# GNSS_BLE.net
KiCad netlist of a schematic drawn in Altium Designer
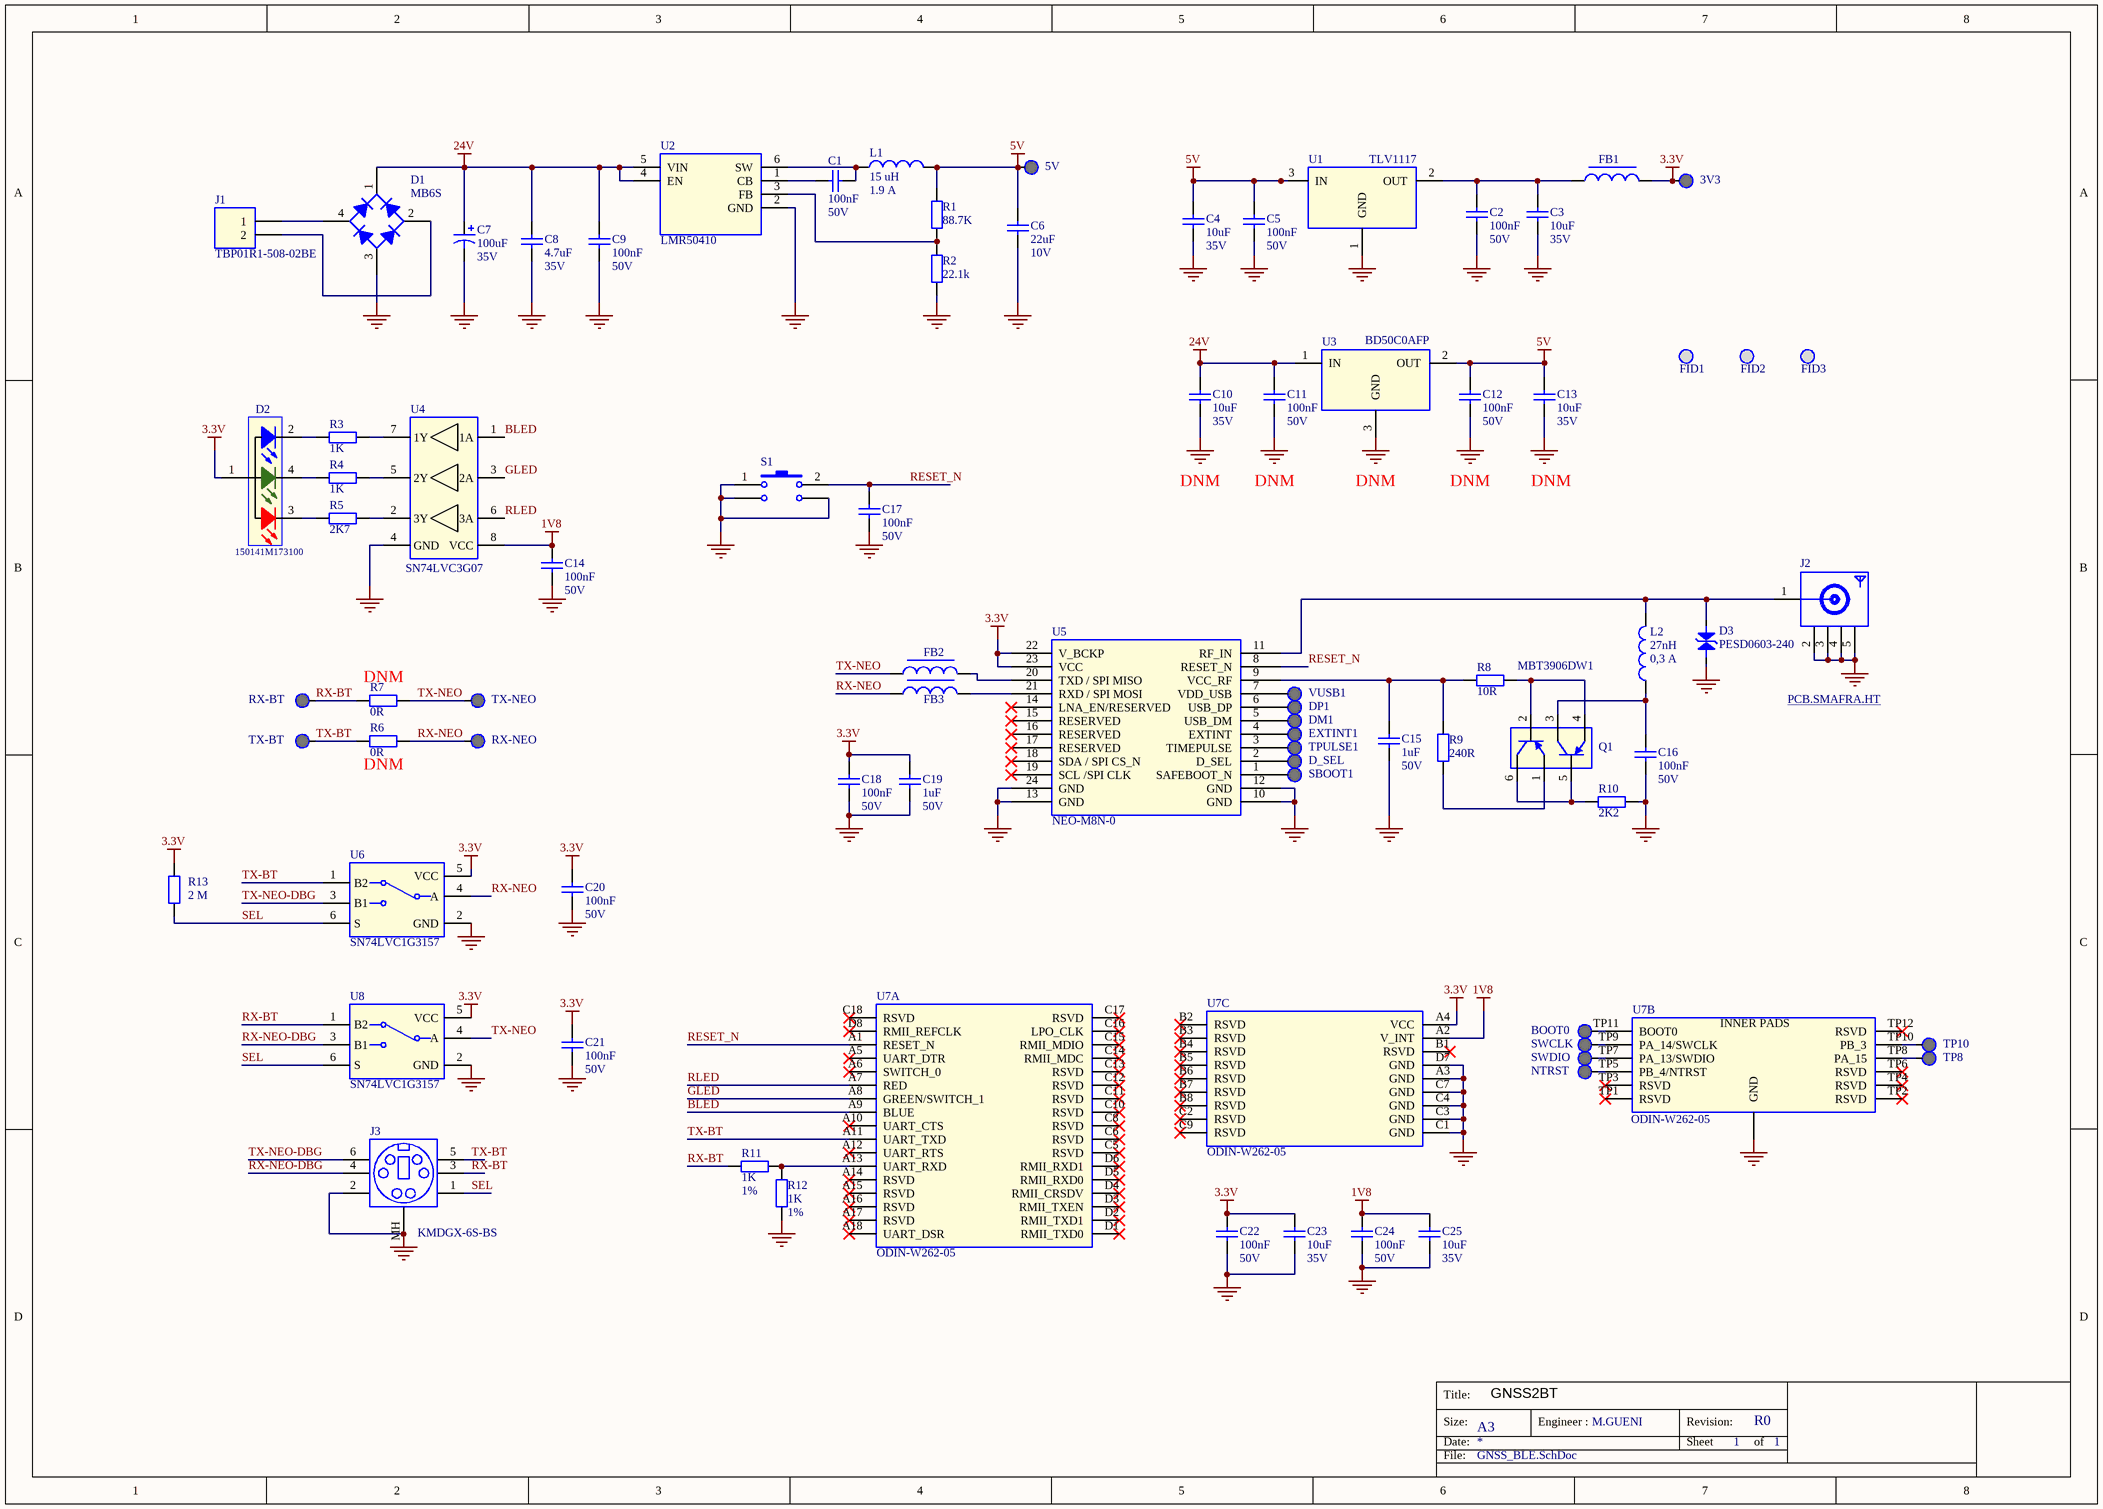
[diagram p0: GNSS_BLE.SchDoc]

(export (version "E")
  (design (tool "Eeschema 10.0.6"))
  (components
    (comp (ref "3V3")
      (value "Test Point")
      (footprint "TP")
      (fields (field (name "PART NUMBER") "MIS-000000001"))
      (libsource (lib "GNSS") (part "TP"))
    )
    (comp (ref "5V")
      (value "Test Point")
      (footprint "TP")
      (fields (field (name "PART NUMBER") "MIS-000000001"))
      (libsource (lib "GNSS") (part "TP"))
    )
    (comp (ref "BOOT0")
      (value "Test Point")
      (footprint "TP")
      (fields (field (name "PART NUMBER") "MIS-000000001"))
      (libsource (lib "GNSS") (part "TP"))
    )
    (comp (ref "C1")
      (value "C0603C104K5RAC3121")
      (footprint "CAPC1608N")
      (fields
        (field (name "PART NUMBER") "CAP-000000001")
        (field (name "VALUE 1") "100nF")
        (field (name "VALUE 2") "50V")
      )
      (libsource (lib "GNSS") (part "Capacitor"))
    )
    (comp (ref "C2")
      (value "C0603C104K5RAC3121")
      (footprint "CAPC1608N")
      (fields
        (field (name "PART NUMBER") "CAP-000000001")
        (field (name "VALUE 1") "100nF")
        (field (name "VALUE 2") "50V")
      )
      (libsource (lib "GNSS") (part "Capacitor"))
    )
    (comp (ref "C3")
      (value "GRM188R6YA106MA73D")
      (footprint "CAPC1608N")
      (fields
        (field (name "PART NUMBER") "CAP-000000003")
        (field (name "VALUE 1") "10uF")
        (field (name "VALUE 2") "35V")
      )
      (libsource (lib "GNSS") (part "Capacitor"))
    )
    (comp (ref "C4")
      (value "GRM188R6YA106MA73D")
      (footprint "CAPC1608N")
      (fields
        (field (name "PART NUMBER") "CAP-000000003")
        (field (name "VALUE 1") "10uF")
        (field (name "VALUE 2") "35V")
      )
      (libsource (lib "GNSS") (part "Capacitor"))
    )
    (comp (ref "C5")
      (value "C0603C104K5RAC3121")
      (footprint "CAPC1608N")
      (fields
        (field (name "PART NUMBER") "CAP-000000001")
        (field (name "VALUE 1") "100nF")
        (field (name "VALUE 2") "50V")
      )
      (libsource (lib "GNSS") (part "Capacitor"))
    )
    (comp (ref "C6")
      (value "GRM188R61A226ME15D")
      (footprint "CAPC1608N")
      (fields
        (field (name "PART NUMBER") "CAP-000000006")
        (field (name "VALUE 1") "22uF")
        (field (name "VALUE 2") "10V")
      )
      (libsource (lib "GNSS") (part "Capacitor"))
    )
    (comp (ref "C7")
      (value "EEEFK1V101XP")
      (footprint "ECAP_SMD_6.3")
      (fields
        (field (name "PART NUMBER") "CAP-000000001")
        (field (name "VALUE 1") "100uF")
        (field (name "VALUE 2") "35V")
      )
      (libsource (lib "GNSS") (part "CPolarized"))
    )
    (comp (ref "C8")
      (value "GRM188R6YA475KE5D")
      (footprint "CAPC1608N")
      (fields
        (field (name "PART NUMBER") "CAP-000000005")
        (field (name "VALUE 1") "4.7uF")
        (field (name "VALUE 2") "35V")
      )
      (libsource (lib "GNSS") (part "Capacitor"))
    )
    (comp (ref "C9")
      (value "C0603C104K5RAC3121")
      (footprint "CAPC1608N")
      (fields
        (field (name "PART NUMBER") "CAP-000000001")
        (field (name "VALUE 1") "100nF")
        (field (name "VALUE 2") "50V")
      )
      (libsource (lib "GNSS") (part "Capacitor"))
    )
    (comp (ref "C10")
      (value "GRM188R6YA106MA73D")
      (footprint "CAPC1608N")
      (fields
        (field (name "PART NUMBER") "CAP-000000003")
        (field (name "VALUE 1") "10uF")
        (field (name "VALUE 2") "35V")
      )
      (libsource (lib "GNSS") (part "Capacitor"))
    )
    (comp (ref "C11")
      (value "C0603C104K5RAC3121")
      (footprint "CAPC1608N")
      (fields
        (field (name "PART NUMBER") "CAP-000000001")
        (field (name "VALUE 1") "100nF")
        (field (name "VALUE 2") "50V")
      )
      (libsource (lib "GNSS") (part "Capacitor"))
    )
    (comp (ref "C12")
      (value "C0603C104K5RAC3121")
      (footprint "CAPC1608N")
      (fields
        (field (name "PART NUMBER") "CAP-000000001")
        (field (name "VALUE 1") "100nF")
        (field (name "VALUE 2") "50V")
      )
      (libsource (lib "GNSS") (part "Capacitor"))
    )
    (comp (ref "C13")
      (value "GRM188R6YA106MA73D")
      (footprint "CAPC1608N")
      (fields
        (field (name "PART NUMBER") "CAP-000000003")
        (field (name "VALUE 1") "10uF")
        (field (name "VALUE 2") "35V")
      )
      (libsource (lib "GNSS") (part "Capacitor"))
    )
    (comp (ref "C14")
      (value "C0603C104K5RAC3121")
      (footprint "CAPC1608N")
      (fields
        (field (name "PART NUMBER") "CAP-000000001")
        (field (name "VALUE 1") "100nF")
        (field (name "VALUE 2") "50V")
      )
      (libsource (lib "GNSS") (part "Capacitor"))
    )
    (comp (ref "C15")
      (value "GRT188R61H105KE13D")
      (footprint "CAPC1608N")
      (fields
        (field (name "PART NUMBER") "CAP-000000004")
        (field (name "VALUE 1") "1uF")
        (field (name "VALUE 2") "50V")
      )
      (libsource (lib "GNSS") (part "Capacitor"))
    )
    (comp (ref "C16")
      (value "C0603C104K5RAC3121")
      (footprint "CAPC1608N")
      (fields
        (field (name "PART NUMBER") "CAP-000000001")
        (field (name "VALUE 1") "100nF")
        (field (name "VALUE 2") "50V")
      )
      (libsource (lib "GNSS") (part "Capacitor"))
    )
    (comp (ref "C17")
      (value "C0603C104K5RAC3121")
      (footprint "CAPC1608N")
      (fields
        (field (name "PART NUMBER") "CAP-000000001")
        (field (name "VALUE 1") "100nF")
        (field (name "VALUE 2") "50V")
      )
      (libsource (lib "GNSS") (part "Capacitor"))
    )
    (comp (ref "C18")
      (value "C0603C104K5RAC3121")
      (footprint "CAPC1608N")
      (fields
        (field (name "PART NUMBER") "CAP-000000001")
        (field (name "VALUE 1") "100nF")
        (field (name "VALUE 2") "50V")
      )
      (libsource (lib "GNSS") (part "Capacitor"))
    )
    (comp (ref "C19")
      (value "GRT188R61H105KE13D")
      (footprint "CAPC1608N")
      (fields
        (field (name "PART NUMBER") "CAP-000000004")
        (field (name "VALUE 1") "1uF")
        (field (name "VALUE 2") "50V")
      )
      (libsource (lib "GNSS") (part "Capacitor"))
    )
    (comp (ref "C20")
      (value "C0603C104K5RAC3121")
      (footprint "CAPC1608N")
      (fields
        (field (name "PART NUMBER") "CAP-000000001")
        (field (name "VALUE 1") "100nF")
        (field (name "VALUE 2") "50V")
      )
      (libsource (lib "GNSS") (part "Capacitor"))
    )
    (comp (ref "C21")
      (value "C0603C104K5RAC3121")
      (footprint "CAPC1608N")
      (fields
        (field (name "PART NUMBER") "CAP-000000001")
        (field (name "VALUE 1") "100nF")
        (field (name "VALUE 2") "50V")
      )
      (libsource (lib "GNSS") (part "Capacitor"))
    )
    (comp (ref "C22")
      (value "C0603C104K5RAC3121")
      (footprint "CAPC1608N")
      (fields
        (field (name "PART NUMBER") "CAP-000000001")
        (field (name "VALUE 1") "100nF")
        (field (name "VALUE 2") "50V")
      )
      (libsource (lib "GNSS") (part "Capacitor"))
    )
    (comp (ref "C23")
      (value "GRM188R6YA106MA73D")
      (footprint "CAPC1608N")
      (fields
        (field (name "PART NUMBER") "CAP-000000003")
        (field (name "VALUE 1") "10uF")
        (field (name "VALUE 2") "35V")
      )
      (libsource (lib "GNSS") (part "Capacitor"))
    )
    (comp (ref "C24")
      (value "C0603C104K5RAC3121")
      (footprint "CAPC1608N")
      (fields
        (field (name "PART NUMBER") "CAP-000000001")
        (field (name "VALUE 1") "100nF")
        (field (name "VALUE 2") "50V")
      )
      (libsource (lib "GNSS") (part "Capacitor"))
    )
    (comp (ref "C25")
      (value "GRM188R6YA106MA73D")
      (footprint "CAPC1608N")
      (fields
        (field (name "PART NUMBER") "CAP-000000003")
        (field (name "VALUE 1") "10uF")
        (field (name "VALUE 2") "35V")
      )
      (libsource (lib "GNSS") (part "Capacitor"))
    )
    (comp (ref "D1")
      (value "MB6S")
      (footprint "MB6S")
      (fields (field (name "PART NUMBER") "DIB-000000001"))
      (libsource (lib "GNSS") (part "DBridge"))
    )
    (comp (ref "D2")
      (value "150141M173100")
      (footprint "150141M173100")
      (fields (field (name "PART NUMBER") "LED-000000001"))
      (libsource (lib "GNSS") (part "150141M173100"))
    )
    (comp (ref "D3")
      (value "PESD0603-240")
      (footprint "TVS1608")
      (fields (field (name "PART NUMBER") "TVS-000000001"))
      (libsource (lib "GNSS") (part "TVS0"))
    )
    (comp (ref "DM1")
      (value "Test Point")
      (footprint "TP")
      (fields (field (name "PART NUMBER") "MIS-000000001"))
      (libsource (lib "GNSS") (part "TP"))
    )
    (comp (ref "DP1")
      (value "Test Point")
      (footprint "TP")
      (fields (field (name "PART NUMBER") "MIS-000000001"))
      (libsource (lib "GNSS") (part "TP"))
    )
    (comp (ref "D_SEL")
      (value "Test Point")
      (footprint "TP")
      (fields (field (name "PART NUMBER") "MIS-000000001"))
      (libsource (lib "GNSS") (part "TP"))
    )
    (comp (ref "EXTINT1")
      (value "Test Point")
      (footprint "TP")
      (fields (field (name "PART NUMBER") "MIS-000000001"))
      (libsource (lib "GNSS") (part "TP"))
    )
    (comp (ref "FB1")
      (value "2512067007Y3")
      (footprint "FB3216")
      (fields (field (name "PART NUMBER") "FER-000000001"))
      (libsource (lib "GNSS") (part "FERRIT"))
    )
    (comp (ref "FB2")
      (value "BLM21BD102SZ1D")
      (footprint "FB2012")
      (fields (field (name "PART NUMBER") "FER-000000002"))
      (libsource (lib "GNSS") (part "FERRIT"))
    )
    (comp (ref "FB3")
      (value "BLM21BD102SZ1D")
      (footprint "FB2012")
      (fields (field (name "PART NUMBER") "FER-000000002"))
      (libsource (lib "GNSS") (part "FERRIT"))
    )
    (comp (ref "FID1")
      (value "Fiducial")
      (footprint "FIDUCIAL-1MM")
      (fields (field (name "PART NUMBER") "MIS-000000002"))
      (libsource (lib "GNSS") (part "Fiducial"))
    )
    (comp (ref "FID2")
      (value "Fiducial")
      (footprint "FIDUCIAL-1MM")
      (fields (field (name "PART NUMBER") "MIS-000000002"))
      (libsource (lib "GNSS") (part "Fiducial"))
    )
    (comp (ref "FID3")
      (value "Fiducial")
      (footprint "FIDUCIAL-1MM")
      (fields (field (name "PART NUMBER") "MIS-000000002"))
      (libsource (lib "GNSS") (part "Fiducial"))
    )
    (comp (ref "J1")
      (value "TBP01R1-508-02BE")
      (footprint "CUI_TBP01R1-508-02BE")
      (fields (field (name "PART NUMBER") "CON-000000001"))
      (libsource (lib "GNSS") (part "Header 2"))
    )
    (comp (ref "J2")
      (value "PCB.SMAFRA.HT")
      (footprint "PCB.SMAFRA.HT")
      (fields (field (name "PART NUMBER") "CON-000000003") (field (name "MANREF") "PCB.SMAFRA.HT"))
      (libsource (lib "GNSS") (part "SMA"))
    )
    (comp (ref "J3")
      (value "KMDGX-6S-BS")
      (footprint "KMDGX6SBS")
      (fields (field (name "PART NUMBER") "CON-000000002"))
      (libsource (lib "GNSS") (part "PS2"))
    )
    (comp (ref "L1")
      (value "74438356150")
      (footprint "IND4020")
      (fields
        (field (name "PART NUMBER") "IND-000000001")
        (field (name "VALUE 1") "15 uH")
        (field (name "VALUE 2") "1.9 A")
      )
      (libsource (lib "GNSS") (part "Inductor"))
    )
    (comp (ref "L2")
      (value "L0603C27NJRMST")
      (footprint "IND1608N")
      (fields
        (field (name "PART NUMBER") "IND-000000002")
        (field (name "VALUE 1") "27nH")
        (field (name "VALUE 2") "0,3 A")
      )
      (libsource (lib "GNSS") (part "Inductor"))
    )
    (comp (ref "NTRST")
      (value "Test Point")
      (footprint "TP")
      (fields (field (name "PART NUMBER") "MIS-000000001"))
      (libsource (lib "GNSS") (part "TP"))
    )
    (comp (ref "Q1")
      (value "MBT3906DW1")
      (footprint "SOT-363-6")
      (fields (field (name "PART NUMBER") "TRP-000000001"))
      (libsource (lib "GNSS") (part "MBT3906DW1T1G"))
    )
    (comp (ref "R1")
      (value "CR0603-FX-8872ELF")
      (footprint "RESC1608N")
      (fields (field (name "PART NUMBER") "RES-000000007") (field (name "VALUE 1") "88.7K"))
      (libsource (lib "") (part "Resistor_1"))
    )
    (comp (ref "R2")
      (value "CRCW060322K1FKEA")
      (footprint "RESC1608N")
      (fields (field (name "PART NUMBER") "RES-000000006") (field (name "VALUE 1") "22.1k"))
      (libsource (lib "") (part "Resistor_1"))
    )
    (comp (ref "R3")
      (value "ERJ-3GEYJ102V")
      (footprint "RESC1608N")
      (fields (field (name "PART NUMBER") "RES-000000001") (field (name "VALUE 1") "1K"))
      (libsource (lib "GNSS") (part "Resistor"))
    )
    (comp (ref "R4")
      (value "ERJ-3GEYJ102V")
      (footprint "RESC1608N")
      (fields (field (name "PART NUMBER") "RES-000000001") (field (name "VALUE 1") "1K"))
      (libsource (lib "GNSS") (part "Resistor"))
    )
    (comp (ref "R5")
      (value "RC0603JR-072K7L")
      (footprint "RESC1608N")
      (fields (field (name "PART NUMBER") "RES-000000009") (field (name "VALUE 1") "2K7"))
      (libsource (lib "GNSS") (part "Resistor"))
    )
    (comp (ref "R6")
      (value "MCT06030Z0000ZP500")
      (footprint "RESC1608N")
      (fields (field (name "PART NUMBER") "RES-000000004") (field (name "VALUE 1") "0R"))
      (libsource (lib "GNSS") (part "Resistor"))
    )
    (comp (ref "R7")
      (value "MCT06030Z0000ZP500")
      (footprint "RESC1608N")
      (fields (field (name "PART NUMBER") "RES-000000004") (field (name "VALUE 1") "0R"))
      (libsource (lib "GNSS") (part "Resistor"))
    )
    (comp (ref "R8")
      (value "CRCW060310R0FKEAC")
      (footprint "RESC1608N")
      (fields (field (name "PART NUMBER") "RES-000000002") (field (name "VALUE 1") "10R"))
      (libsource (lib "") (part "Resistor_2"))
    )
    (comp (ref "R9")
      (value "CRCW0603240RFKEA")
      (footprint "RESC1608N")
      (fields (field (name "PART NUMBER") "RES-000000005") (field (name "VALUE 1") "240R"))
      (libsource (lib "") (part "Resistor_1"))
    )
    (comp (ref "R10")
      (value "RC0603JR-072K2L")
      (footprint "RESC1608N")
      (fields (field (name "PART NUMBER") "RES-000000003") (field (name "VALUE 1") "2K2"))
      (libsource (lib "GNSS") (part "Resistor"))
    )
    (comp (ref "R11")
      (value "ERJ-3GEYJ102V")
      (footprint "RESC1608N")
      (fields
        (field (name "PART NUMBER") "RES-000000001")
        (field (name "VALUE 1") "1K")
        (field (name "TOL") "1%")
      )
      (libsource (lib "") (part "Resistor_2"))
    )
    (comp (ref "R12")
      (value "ERJ-3GEYJ102V")
      (footprint "RESC1608N")
      (fields
        (field (name "PART NUMBER") "RES-000000001")
        (field (name "VALUE 1") "1K")
        (field (name "TOL") "1%")
      )
      (libsource (lib "") (part "Resistor_3"))
    )
    (comp (ref "R13")
      (value "MCT06030C2004FP500")
      (footprint "RESC1608N")
      (fields (field (name "PART NUMBER") "RES-000000008") (field (name "VALUE 1") "2 M"))
      (libsource (lib "") (part "Resistor_3"))
    )
    (comp (ref "RX-BT")
      (value "Test Point")
      (footprint "TP")
      (fields (field (name "PART NUMBER") "MIS-000000001"))
      (libsource (lib "GNSS") (part "TP"))
    )
    (comp (ref "RX-NEO")
      (value "Test Point")
      (footprint "TP")
      (fields (field (name "PART NUMBER") "MIS-000000001"))
      (libsource (lib "GNSS") (part "TP"))
    )
    (comp (ref "S1")
      (value "1825027-8")
      (footprint "218250270")
      (fields (field (name "PART NUMBER") "SWC-000000001"))
      (libsource (lib "GNSS") (part "SW-PB"))
    )
    (comp (ref "SBOOT1")
      (value "Test Point")
      (footprint "TP")
      (fields (field (name "PART NUMBER") "MIS-000000001"))
      (libsource (lib "GNSS") (part "TP"))
    )
    (comp (ref "SWCLK")
      (value "Test Point")
      (footprint "TP")
      (fields (field (name "PART NUMBER") "MIS-000000001"))
      (libsource (lib "GNSS") (part "TP"))
    )
    (comp (ref "SWDIO")
      (value "Test Point")
      (footprint "TP")
      (fields (field (name "PART NUMBER") "MIS-000000001"))
      (libsource (lib "GNSS") (part "TP"))
    )
    (comp (ref "TP8")
      (value "Test Point")
      (footprint "TP")
      (fields (field (name "PART NUMBER") "MIS-000000001"))
      (libsource (lib "GNSS") (part "TP"))
    )
    (comp (ref "TP10")
      (value "Test Point")
      (footprint "TP")
      (fields (field (name "PART NUMBER") "MIS-000000001"))
      (libsource (lib "GNSS") (part "TP"))
    )
    (comp (ref "TPULSE1")
      (value "Test Point")
      (footprint "TP")
      (fields (field (name "PART NUMBER") "MIS-000000001"))
      (libsource (lib "GNSS") (part "TP"))
    )
    (comp (ref "TX-BT")
      (value "Test Point")
      (footprint "TP")
      (fields (field (name "PART NUMBER") "MIS-000000001"))
      (libsource (lib "GNSS") (part "TP"))
    )
    (comp (ref "TX-NEO")
      (value "Test Point")
      (footprint "TP")
      (fields (field (name "PART NUMBER") "MIS-000000001"))
      (libsource (lib "GNSS") (part "TP"))
    )
    (comp (ref "U1")
      (value "TLV1117")
      (footprint "SOT223")
      (fields (field (name "PART NUMBER") "VRG-000000001"))
      (libsource (lib "GNSS") (part "TLV1117"))
    )
    (comp (ref "U2")
      (value "LMR50410")
      (footprint "SOT-23-6")
      (fields (field (name "PART NUMBER") "ICP-000000001"))
      (libsource (lib "GNSS") (part "LMR50410Y"))
    )
    (comp (ref "U3")
      (value "BD50C0AFP")
      (footprint "TO-252-3")
      (fields (field (name "PART NUMBER") "VRG-000000003"))
      (libsource (lib "GNSS") (part "BD50C0AFP"))
    )
    (comp (ref "U4")
      (value "SN74LVC3G07")
      (footprint "VSSOP-8")
      (fields (field (name "PART NUMBER") "ICD-000000001"))
      (libsource (lib "GNSS") (part "SN74LVC3G07"))
    )
    (comp (ref "U5")
      (value "NEO-M8N-0")
      (footprint "NEO-M8N")
      (fields (field (name "PART NUMBER") "RFC-000000001"))
      (libsource (lib "GNSS") (part "NEO-M8"))
    )
    (comp (ref "U6")
      (value "SN74LVC1G3157")
      (footprint "SOT-23-6")
      (fields (field (name "PART NUMBER") "GIC-000000001"))
      (libsource (lib "GNSS") (part "SN74LVC1G3157"))
    )
    (comp (ref "U7")
      (value "ODIN-W262-05")
      (footprint "ODIN-W26")
      (fields (field (name "PART NUMBER") "RFC-000000002"))
      (libsource (lib "GNSS") (part "ODIN-W26"))
    )
    (comp (ref "U8")
      (value "SN74LVC1G3157")
      (footprint "SOT-23-6")
      (fields (field (name "PART NUMBER") "GIC-000000001"))
      (libsource (lib "GNSS") (part "SN74LVC1G3157"))
    )
    (comp (ref "VUSB1")
      (value "Test Point")
      (footprint "TP")
      (fields (field (name "PART NUMBER") "MIS-000000001"))
      (libsource (lib "GNSS") (part "TP"))
    )
  )
  (nets
    (net (code "1") (name "/BLED") (class "Default")
      (node (ref "U4") (pin "1") (pinfunction "1A_1") (pintype "passive"))
      (node (ref "U7") (pin "A9") (pinfunction "BLUE_A9") (pintype "passive"))
    )
    (net (code "2") (name "/GLED") (class "Default")
      (node (ref "U4") (pin "3") (pinfunction "2A_3") (pintype "passive"))
      (node (ref "U7") (pin "A8") (pinfunction "GREEN/SWITCH_1_A8") (pintype "passive"))
    )
    (net (code "3") (name "/RESET_N") (class "Default")
      (node (ref "C17") (pin "1") (pinfunction "1_1") (pintype "passive"))
      (node (ref "S1") (pin "2") (pinfunction "2_2") (pintype "passive"))
      (node (ref "U5") (pin "8") (pinfunction "RESET_N_8") (pintype "passive"))
      (node (ref "U7") (pin "A1") (pinfunction "RESET_N_A1") (pintype "passive"))
    )
    (net (code "4") (name "/RLED") (class "Default")
      (node (ref "U4") (pin "6") (pinfunction "3A_6") (pintype "passive"))
      (node (ref "U7") (pin "A7") (pinfunction "RED_A7") (pintype "passive"))
    )
    (net (code "5") (name "/RX-BT") (class "Default")
      (node (ref "J3") (pin "3") (pinfunction "3_3") (pintype "passive"))
      (node (ref "R11") (pin "1") (pinfunction "1_1") (pintype "passive"))
      (node (ref "R7") (pin "2") (pinfunction "2_2") (pintype "passive"))
      (node (ref "RX-BT") (pin "1") (pinfunction "1_1") (pintype "passive"))
      (node (ref "U8") (pin "1") (pinfunction "B2_1") (pintype "passive"))
    )
    (net (code "6") (name "/RX-NEO") (class "Default")
      (node (ref "FB3") (pin "1") (pinfunction "1_1") (pintype "passive"))
      (node (ref "R6") (pin "1") (pinfunction "1_1") (pintype "passive"))
      (node (ref "RX-NEO") (pin "1") (pinfunction "1_1") (pintype "passive"))
      (node (ref "U6") (pin "4") (pinfunction "A_4") (pintype "passive"))
    )
    (net (code "7") (name "/RX-NEO-DBG") (class "Default")
      (node (ref "J3") (pin "4") (pinfunction "4_4") (pintype "passive"))
      (node (ref "U8") (pin "3") (pinfunction "B1_3") (pintype "passive"))
    )
    (net (code "8") (name "/SEL") (class "Default")
      (node (ref "J3") (pin "1") (pinfunction "1_1") (pintype "passive"))
      (node (ref "R13") (pin "1") (pinfunction "1_1") (pintype "passive"))
      (node (ref "U6") (pin "6") (pinfunction "S_6") (pintype "passive"))
      (node (ref "U8") (pin "6") (pinfunction "S_6") (pintype "passive"))
    )
    (net (code "9") (name "/TX-BT") (class "Default")
      (node (ref "J3") (pin "5") (pinfunction "5_5") (pintype "passive"))
      (node (ref "R6") (pin "2") (pinfunction "2_2") (pintype "passive"))
      (node (ref "TX-BT") (pin "1") (pinfunction "1_1") (pintype "passive"))
      (node (ref "U6") (pin "1") (pinfunction "B2_1") (pintype "passive"))
      (node (ref "U7") (pin "A11") (pinfunction "UART_TXD_A11") (pintype "passive"))
    )
    (net (code "10") (name "/TX-NEO") (class "Default")
      (node (ref "FB2") (pin "1") (pinfunction "1_1") (pintype "passive"))
      (node (ref "R7") (pin "1") (pinfunction "1_1") (pintype "passive"))
      (node (ref "TX-NEO") (pin "1") (pinfunction "1_1") (pintype "passive"))
      (node (ref "U8") (pin "4") (pinfunction "A_4") (pintype "passive"))
    )
    (net (code "11") (name "/TX-NEO-DBG") (class "Default")
      (node (ref "J3") (pin "6") (pinfunction "6_6") (pintype "passive"))
      (node (ref "U6") (pin "3") (pinfunction "B1_3") (pintype "passive"))
    )
    (net (code "12") (name "1V8") (class "Default")
      (node (ref "C14") (pin "1") (pinfunction "1_1") (pintype "passive"))
      (node (ref "C24") (pin "2") (pinfunction "2_2") (pintype "passive"))
      (node (ref "C25") (pin "2") (pinfunction "2_2") (pintype "passive"))
      (node (ref "U4") (pin "8") (pinfunction "VCC_8") (pintype "passive"))
      (node (ref "U7") (pin "A2") (pinfunction "V_INT_A2") (pintype "passive"))
    )
    (net (code "13") (name "3.3V") (class "Default")
      (node (ref "3V3") (pin "1") (pinfunction "1_1") (pintype "passive"))
      (node (ref "C18") (pin "1") (pinfunction "1_1") (pintype "passive"))
      (node (ref "C19") (pin "1") (pinfunction "1_1") (pintype "passive"))
      (node (ref "C20") (pin "2") (pinfunction "2_2") (pintype "passive"))
      (node (ref "C21") (pin "2") (pinfunction "2_2") (pintype "passive"))
      (node (ref "C22") (pin "2") (pinfunction "2_2") (pintype "passive"))
      (node (ref "C23") (pin "2") (pinfunction "2_2") (pintype "passive"))
      (node (ref "D2") (pin "1") (pinfunction "A_1") (pintype "passive"))
      (node (ref "FB1") (pin "2") (pinfunction "2_2") (pintype "passive"))
      (node (ref "R13") (pin "2") (pinfunction "2_2") (pintype "passive"))
      (node (ref "U5") (pin "22") (pinfunction "V_BCKP_22") (pintype "passive"))
      (node (ref "U5") (pin "23") (pinfunction "VCC_23") (pintype "passive"))
      (node (ref "U6") (pin "5") (pinfunction "VCC_5") (pintype "passive"))
      (node (ref "U7") (pin "A4") (pinfunction "VCC_A4") (pintype "passive"))
      (node (ref "U8") (pin "5") (pinfunction "VCC_5") (pintype "passive"))
    )
    (net (code "14") (name "5V") (class "Default")
      (node (ref "5V") (pin "1") (pinfunction "1_1") (pintype "passive"))
      (node (ref "C12") (pin "1") (pinfunction "1_1") (pintype "passive"))
      (node (ref "C13") (pin "2") (pinfunction "2_2") (pintype "passive"))
      (node (ref "C4") (pin "1") (pinfunction "1_1") (pintype "passive"))
      (node (ref "C5") (pin "1") (pinfunction "1_1") (pintype "passive"))
      (node (ref "C6") (pin "1") (pinfunction "1_1") (pintype "passive"))
      (node (ref "L1") (pin "2") (pinfunction "2_2") (pintype "passive"))
      (node (ref "R1") (pin "1") (pinfunction "1_1") (pintype "passive"))
      (node (ref "U1") (pin "3") (pinfunction "IN_3") (pintype "passive"))
      (node (ref "U3") (pin "2") (pinfunction "OUT_2") (pintype "passive"))
    )
    (net (code "15") (name "24V") (class "Default")
      (node (ref "C10") (pin "1") (pinfunction "1_1") (pintype "passive"))
      (node (ref "C11") (pin "2") (pinfunction "2_2") (pintype "passive"))
      (node (ref "C7") (pin "1") (pinfunction "1_1") (pintype "passive"))
      (node (ref "C8") (pin "1") (pinfunction "1_1") (pintype "passive"))
      (node (ref "C9") (pin "1") (pinfunction "1_1") (pintype "passive"))
      (node (ref "D1") (pin "1") (pinfunction "K_1") (pintype "passive"))
      (node (ref "U2") (pin "4") (pinfunction "EN_4") (pintype "passive"))
      (node (ref "U2") (pin "5") (pinfunction "VIN_5") (pintype "passive"))
      (node (ref "U3") (pin "1") (pinfunction "IN_1") (pintype "passive"))
    )
    (net (code "16") (name "GND") (class "Default")
      (node (ref "C10") (pin "2") (pinfunction "2_2") (pintype "passive"))
      (node (ref "C11") (pin "1") (pinfunction "1_1") (pintype "passive"))
      (node (ref "C12") (pin "2") (pinfunction "2_2") (pintype "passive"))
      (node (ref "C13") (pin "1") (pinfunction "1_1") (pintype "passive"))
      (node (ref "C14") (pin "2") (pinfunction "2_2") (pintype "passive"))
      (node (ref "C15") (pin "2") (pinfunction "2_2") (pintype "passive"))
      (node (ref "C16") (pin "1") (pinfunction "1_1") (pintype "passive"))
      (node (ref "C17") (pin "2") (pinfunction "2_2") (pintype "passive"))
      (node (ref "C18") (pin "2") (pinfunction "2_2") (pintype "passive"))
      (node (ref "C19") (pin "2") (pinfunction "2_2") (pintype "passive"))
      (node (ref "C2") (pin "2") (pinfunction "2_2") (pintype "passive"))
      (node (ref "C20") (pin "1") (pinfunction "1_1") (pintype "passive"))
      (node (ref "C21") (pin "1") (pinfunction "1_1") (pintype "passive"))
      (node (ref "C22") (pin "1") (pinfunction "1_1") (pintype "passive"))
      (node (ref "C23") (pin "1") (pinfunction "1_1") (pintype "passive"))
      (node (ref "C24") (pin "1") (pinfunction "1_1") (pintype "passive"))
      (node (ref "C25") (pin "1") (pinfunction "1_1") (pintype "passive"))
      (node (ref "C3") (pin "2") (pinfunction "2_2") (pintype "passive"))
      (node (ref "C4") (pin "2") (pinfunction "2_2") (pintype "passive"))
      (node (ref "C5") (pin "2") (pinfunction "2_2") (pintype "passive"))
      (node (ref "C6") (pin "2") (pinfunction "2_2") (pintype "passive"))
      (node (ref "C7") (pin "2") (pinfunction "2_2") (pintype "passive"))
      (node (ref "C8") (pin "2") (pinfunction "2_2") (pintype "passive"))
      (node (ref "C9") (pin "2") (pinfunction "2_2") (pintype "passive"))
      (node (ref "D1") (pin "3") (pinfunction "A_3") (pintype "passive"))
      (node (ref "D3") (pin "1") (pinfunction "1_1") (pintype "passive"))
      (node (ref "J2") (pin "2") (pinfunction "2_2") (pintype "passive"))
      (node (ref "J2") (pin "3") (pinfunction "3_3") (pintype "passive"))
      (node (ref "J2") (pin "4") (pinfunction "4_4") (pintype "passive"))
      (node (ref "J2") (pin "5") (pinfunction "5_5") (pintype "passive"))
      (node (ref "J3") (pin "2") (pinfunction "2_2") (pintype "passive"))
      (node (ref "J3") (pin "MH") (pinfunction "MH_MH") (pintype "passive"))
      (node (ref "R10") (pin "1") (pinfunction "1_1") (pintype "passive"))
      (node (ref "R12") (pin "1") (pinfunction "1_1") (pintype "passive"))
      (node (ref "R2") (pin "2") (pinfunction "2_2") (pintype "passive"))
      (node (ref "S1") (pin "1") (pinfunction "1_1") (pintype "passive"))
      (node (ref "S1") (pin "MH") (pinfunction "MH_MH") (pintype "passive"))
      (node (ref "U1") (pin "1") (pinfunction "GND_1") (pintype "passive"))
      (node (ref "U2") (pin "2") (pinfunction "GND_2") (pintype "passive"))
      (node (ref "U3") (pin "3") (pinfunction "GND_3") (pintype "passive"))
      (node (ref "U4") (pin "4") (pinfunction "GND_4") (pintype "passive"))
      (node (ref "U5") (pin "10") (pinfunction "GND_10") (pintype "passive"))
      (node (ref "U5") (pin "12") (pinfunction "GND_12") (pintype "passive"))
      (node (ref "U5") (pin "13") (pinfunction "GND_13") (pintype "passive"))
      (node (ref "U5") (pin "24") (pinfunction "GND_24") (pintype "passive"))
      (node (ref "U6") (pin "2") (pinfunction "GND_2") (pintype "passive"))
      (node (ref "U7") (pin "A3") (pinfunction "GND_A3") (pintype "passive"))
      (node (ref "U7") (pin "C1") (pinfunction "GND_C1") (pintype "passive"))
      (node (ref "U7") (pin "C3") (pinfunction "GND_C3") (pintype "passive"))
      (node (ref "U7") (pin "C4") (pinfunction "GND_C4") (pintype "passive"))
      (node (ref "U7") (pin "C7") (pinfunction "GND_C7") (pintype "passive"))
      (node (ref "U7") (pin "D7") (pinfunction "GND_D7") (pintype "passive"))
      (node (ref "U7") (pin "GND") (pinfunction "GND_GND") (pintype "passive"))
      (node (ref "U8") (pin "2") (pinfunction "GND_2") (pintype "passive"))
    )
    (net (code "17") (name "Net-(D1-C-Pad2)") (class "Default")
      (node (ref "D1") (pin "2") (pinfunction "C_2") (pintype "passive"))
      (node (ref "J1") (pin "2") (pinfunction "2_2") (pintype "passive"))
    )
    (net (code "18") (name "Net-(D1-C-Pad4)") (class "Default")
      (node (ref "D1") (pin "4") (pinfunction "C_4") (pintype "passive"))
      (node (ref "J1") (pin "1") (pinfunction "1_1") (pintype "passive"))
    )
    (net (code "19") (name "Net-(D2-K-Pad2)") (class "Default")
      (node (ref "D2") (pin "2") (pinfunction "K_2") (pintype "passive"))
      (node (ref "R3") (pin "2") (pinfunction "2_2") (pintype "passive"))
    )
    (net (code "20") (name "Net-(D2-K-Pad3)") (class "Default")
      (node (ref "D2") (pin "3") (pinfunction "K_3") (pintype "passive"))
      (node (ref "R5") (pin "2") (pinfunction "2_2") (pintype "passive"))
    )
    (net (code "21") (name "Net-(D2-K-Pad4)") (class "Default")
      (node (ref "D2") (pin "4") (pinfunction "K_4") (pintype "passive"))
      (node (ref "R4") (pin "2") (pinfunction "2_2") (pintype "passive"))
    )
    (net (code "22") (name "Net-(D3-K1A2)") (class "Default")
      (node (ref "D3") (pin "2") (pinfunction "K1A2_2") (pintype "passive"))
      (node (ref "J2") (pin "1") (pinfunction "1_1") (pintype "passive"))
      (node (ref "L2") (pin "2") (pinfunction "2_2") (pintype "passive"))
      (node (ref "U5") (pin "11") (pinfunction "RF_IN_11") (pintype "passive"))
    )
    (net (code "23") (name "Net-(Q1-B1)") (class "Default")
      (node (ref "Q1") (pin "5") (pinfunction "B1_5") (pintype "passive"))
      (node (ref "Q1") (pin "6") (pinfunction "C2_6") (pintype "passive"))
      (node (ref "R10") (pin "2") (pinfunction "2_2") (pintype "passive"))
    )
    (net (code "24") (name "Net-(Q1-B2)") (class "Default")
      (node (ref "Q1") (pin "2") (pinfunction "B2_2") (pintype "passive"))
      (node (ref "Q1") (pin "4") (pinfunction "E1_4") (pintype "passive"))
      (node (ref "R8") (pin "2") (pinfunction "2_2") (pintype "passive"))
    )
    (net (code "25") (name "Net-(Q1-C1)") (class "Default")
      (node (ref "C16") (pin "2") (pinfunction "2_2") (pintype "passive"))
      (node (ref "L2") (pin "1") (pinfunction "1_1") (pintype "passive"))
      (node (ref "Q1") (pin "3") (pinfunction "C1_3") (pintype "passive"))
    )
    (net (code "26") (name "Net-(Q1-E2)") (class "Default")
      (node (ref "Q1") (pin "1") (pinfunction "E2_1") (pintype "passive"))
      (node (ref "R9") (pin "2") (pinfunction "2_2") (pintype "passive"))
    )
    (net (code "27") (name "Net-(U1-OUT)") (class "Default")
      (node (ref "C2") (pin "1") (pinfunction "1_1") (pintype "passive"))
      (node (ref "C3") (pin "1") (pinfunction "1_1") (pintype "passive"))
      (node (ref "FB1") (pin "1") (pinfunction "1_1") (pintype "passive"))
      (node (ref "U1") (pin "2") (pinfunction "OUT_2") (pintype "passive"))
    )
    (net (code "28") (name "Net-(U2-CB)") (class "Default")
      (node (ref "C1") (pin "1") (pinfunction "1_1") (pintype "passive"))
      (node (ref "U2") (pin "1") (pinfunction "CB_1") (pintype "passive"))
    )
    (net (code "29") (name "Net-(U2-FB)") (class "Default")
      (node (ref "R1") (pin "2") (pinfunction "2_2") (pintype "passive"))
      (node (ref "R2") (pin "1") (pinfunction "1_1") (pintype "passive"))
      (node (ref "U2") (pin "3") (pinfunction "FB_3") (pintype "passive"))
    )
    (net (code "30") (name "Net-(U2-SW)") (class "Default")
      (node (ref "C1") (pin "2") (pinfunction "2_2") (pintype "passive"))
      (node (ref "L1") (pin "1") (pinfunction "1_1") (pintype "passive"))
      (node (ref "U2") (pin "6") (pinfunction "SW_6") (pintype "passive"))
    )
    (net (code "31") (name "Net-(U4-1Y)") (class "Default")
      (node (ref "R3") (pin "1") (pinfunction "1_1") (pintype "passive"))
      (node (ref "U4") (pin "7") (pinfunction "1Y_7") (pintype "passive"))
    )
    (net (code "32") (name "Net-(U4-2Y)") (class "Default")
      (node (ref "R4") (pin "1") (pinfunction "1_1") (pintype "passive"))
      (node (ref "U4") (pin "5") (pinfunction "2Y_5") (pintype "passive"))
    )
    (net (code "33") (name "Net-(U4-3Y)") (class "Default")
      (node (ref "R5") (pin "1") (pinfunction "1_1") (pintype "passive"))
      (node (ref "U4") (pin "2") (pinfunction "3Y_2") (pintype "passive"))
    )
    (net (code "34") (name "Net-(U5-D_SEL)") (class "Default")
      (node (ref "D_SEL") (pin "1") (pinfunction "1_1") (pintype "passive"))
      (node (ref "U5") (pin "2") (pinfunction "D_SEL_2") (pintype "passive"))
    )
    (net (code "35") (name "Net-(U5-EXTINT)") (class "Default")
      (node (ref "EXTINT1") (pin "1") (pinfunction "1_1") (pintype "passive"))
      (node (ref "U5") (pin "4") (pinfunction "EXTINT_4") (pintype "passive"))
    )
    (net (code "36") (name "Net-(U5-RXD_{slash}_SPI_MOSI)") (class "Default")
      (node (ref "FB3") (pin "2") (pinfunction "2_2") (pintype "passive"))
      (node (ref "U5") (pin "21") (pinfunction "RXD_/_SPI_MOSI_21") (pintype "passive"))
    )
    (net (code "37") (name "Net-(U5-SAFEBOOT_N)") (class "Default")
      (node (ref "SBOOT1") (pin "1") (pinfunction "1_1") (pintype "passive"))
      (node (ref "U5") (pin "1") (pinfunction "SAFEBOOT_N_1") (pintype "passive"))
    )
    (net (code "38") (name "Net-(U5-TIMEPULSE)") (class "Default")
      (node (ref "TPULSE1") (pin "1") (pinfunction "1_1") (pintype "passive"))
      (node (ref "U5") (pin "3") (pinfunction "TIMEPULSE_3") (pintype "passive"))
    )
    (net (code "39") (name "Net-(U5-TXD_{slash}_SPI_MISO)") (class "Default")
      (node (ref "FB2") (pin "2") (pinfunction "2_2") (pintype "passive"))
      (node (ref "U5") (pin "20") (pinfunction "TXD_/_SPI_MISO_20") (pintype "passive"))
    )
    (net (code "40") (name "Net-(U5-USB_DM)") (class "Default")
      (node (ref "DM1") (pin "1") (pinfunction "1_1") (pintype "passive"))
      (node (ref "U5") (pin "5") (pinfunction "USB_DM_5") (pintype "passive"))
    )
    (net (code "41") (name "Net-(U5-USB_DP)") (class "Default")
      (node (ref "DP1") (pin "1") (pinfunction "1_1") (pintype "passive"))
      (node (ref "U5") (pin "6") (pinfunction "USB_DP_6") (pintype "passive"))
    )
    (net (code "42") (name "Net-(U5-VCC_RF)") (class "Default")
      (node (ref "C15") (pin "1") (pinfunction "1_1") (pintype "passive"))
      (node (ref "R8") (pin "1") (pinfunction "1_1") (pintype "passive"))
      (node (ref "R9") (pin "1") (pinfunction "1_1") (pintype "passive"))
      (node (ref "U5") (pin "9") (pinfunction "VCC_RF_9") (pintype "passive"))
    )
    (net (code "43") (name "Net-(U5-VDD_USB)") (class "Default")
      (node (ref "U5") (pin "7") (pinfunction "VDD_USB_7") (pintype "passive"))
      (node (ref "VUSB1") (pin "1") (pinfunction "1_1") (pintype "passive"))
    )
    (net (code "44") (name "Net-(U7A-UART_RXD)") (class "Default")
      (node (ref "R11") (pin "2") (pinfunction "2_2") (pintype "passive"))
      (node (ref "R12") (pin "2") (pinfunction "2_2") (pintype "passive"))
      (node (ref "U7") (pin "A13") (pinfunction "UART_RXD_A13") (pintype "passive"))
    )
    (net (code "45") (name "Net-(U7B-BOOT0)") (class "Default")
      (node (ref "BOOT0") (pin "1") (pinfunction "1_1") (pintype "passive"))
      (node (ref "U7") (pin "TP11") (pinfunction "BOOT0_TP11") (pintype "passive"))
    )
    (net (code "46") (name "Net-(U7B-PA_13{slash}SWDIO)") (class "Default")
      (node (ref "SWDIO") (pin "1") (pinfunction "1_1") (pintype "passive"))
      (node (ref "U7") (pin "TP7") (pinfunction "PA_13/SWDIO_TP7") (pintype "passive"))
    )
    (net (code "47") (name "Net-(U7B-PA_14{slash}SWCLK)") (class "Default")
      (node (ref "SWCLK") (pin "1") (pinfunction "1_1") (pintype "passive"))
      (node (ref "U7") (pin "TP9") (pinfunction "PA_14/SWCLK_TP9") (pintype "passive"))
    )
    (net (code "48") (name "Net-(U7B-PA_15)") (class "Default")
      (node (ref "TP8") (pin "1") (pinfunction "1_1") (pintype "passive"))
      (node (ref "U7") (pin "TP8") (pinfunction "PA_15_TP8") (pintype "passive"))
    )
    (net (code "49") (name "Net-(U7B-PB_3)") (class "Default")
      (node (ref "TP10") (pin "1") (pinfunction "1_1") (pintype "passive"))
      (node (ref "U7") (pin "TP10") (pinfunction "PB_3_TP10") (pintype "passive"))
    )
    (net (code "50") (name "Net-(U7B-PB_4{slash}NTRST)") (class "Default")
      (node (ref "NTRST") (pin "1") (pinfunction "1_1") (pintype "passive"))
      (node (ref "U7") (pin "TP5") (pinfunction "PB_4/NTRST_TP5") (pintype "passive"))
    )
    (net (code "51") (name "unconnected-(U5-LNA_EN{slash}RESERVED-Pad14)") (class "Default")
      (node (ref "U5") (pin "14") (pinfunction "LNA_EN/RESERVED_14") (pintype "passive+no_connect"))
    )
    (net (code "52") (name "unconnected-(U5-RESERVED-Pad15)") (class "Default")
      (node (ref "U5") (pin "15") (pinfunction "RESERVED_15") (pintype "passive+no_connect"))
    )
    (net (code "53") (name "unconnected-(U5-RESERVED-Pad16)") (class "Default")
      (node (ref "U5") (pin "16") (pinfunction "RESERVED_16") (pintype "passive+no_connect"))
    )
    (net (code "54") (name "unconnected-(U5-RESERVED-Pad17)") (class "Default")
      (node (ref "U5") (pin "17") (pinfunction "RESERVED_17") (pintype "passive+no_connect"))
    )
    (net (code "55") (name "unconnected-(U5-SCL_{slash}SPI_CLK-Pad19)") (class "Default")
      (node (ref "U5") (pin "19") (pinfunction "SCL_/SPI_CLK_19") (pintype "passive+no_connect"))
    )
    (net (code "56") (name "unconnected-(U5-SDA_{slash}_SPI_CS_N-Pad18)") (class "Default")
      (node (ref "U5") (pin "18") (pinfunction "SDA_/_SPI_CS_N_18") (pintype "passive+no_connect"))
    )
    (net (code "57") (name "unconnected-(U7A-LPO_CLK-PadC16)") (class "Default")
      (node (ref "U7") (pin "C16") (pinfunction "LPO_CLK_C16") (pintype "passive+no_connect"))
    )
    (net (code "58") (name "unconnected-(U7A-RMII_CRSDV-PadD4)") (class "Default")
      (node (ref "U7") (pin "D4") (pinfunction "RMII_CRSDV_D4") (pintype "passive+no_connect"))
    )
    (net (code "59") (name "unconnected-(U7A-RMII_MDC-PadC14)") (class "Default")
      (node (ref "U7") (pin "C14") (pinfunction "RMII_MDC_C14") (pintype "passive+no_connect"))
    )
    (net (code "60") (name "unconnected-(U7A-RMII_MDIO-PadC15)") (class "Default")
      (node (ref "U7") (pin "C15") (pinfunction "RMII_MDIO_C15") (pintype "passive+no_connect"))
    )
    (net (code "61") (name "unconnected-(U7A-RMII_REFCLK-PadD8)") (class "Default")
      (node (ref "U7") (pin "D8") (pinfunction "RMII_REFCLK_D8") (pintype "passive+no_connect"))
    )
    (net (code "62") (name "unconnected-(U7A-RMII_RXD0-PadD5)") (class "Default")
      (node (ref "U7") (pin "D5") (pinfunction "RMII_RXD0_D5") (pintype "passive+no_connect"))
    )
    (net (code "63") (name "unconnected-(U7A-RMII_RXD1-PadD6)") (class "Default")
      (node (ref "U7") (pin "D6") (pinfunction "RMII_RXD1_D6") (pintype "passive+no_connect"))
    )
    (net (code "64") (name "unconnected-(U7A-RMII_TXD0-PadD1)") (class "Default")
      (node (ref "U7") (pin "D1") (pinfunction "RMII_TXD0_D1") (pintype "passive+no_connect"))
    )
    (net (code "65") (name "unconnected-(U7A-RMII_TXD1-PadD2)") (class "Default")
      (node (ref "U7") (pin "D2") (pinfunction "RMII_TXD1_D2") (pintype "passive+no_connect"))
    )
    (net (code "66") (name "unconnected-(U7A-RMII_TXEN-PadD3)") (class "Default")
      (node (ref "U7") (pin "D3") (pinfunction "RMII_TXEN_D3") (pintype "passive+no_connect"))
    )
    (net (code "67") (name "unconnected-(U7A-RSVD-PadA14)") (class "Default")
      (node (ref "U7") (pin "A14") (pinfunction "RSVD_A14") (pintype "passive+no_connect"))
    )
    (net (code "68") (name "unconnected-(U7A-RSVD-PadA15)") (class "Default")
      (node (ref "U7") (pin "A15") (pinfunction "RSVD_A15") (pintype "passive+no_connect"))
    )
    (net (code "69") (name "unconnected-(U7A-RSVD-PadA16)") (class "Default")
      (node (ref "U7") (pin "A16") (pinfunction "RSVD_A16") (pintype "passive+no_connect"))
    )
    (net (code "70") (name "unconnected-(U7A-RSVD-PadA17)") (class "Default")
      (node (ref "U7") (pin "A17") (pinfunction "RSVD_A17") (pintype "passive+no_connect"))
    )
    (net (code "71") (name "unconnected-(U7A-RSVD-PadC5)") (class "Default")
      (node (ref "U7") (pin "C5") (pinfunction "RSVD_C5") (pintype "passive+no_connect"))
    )
    (net (code "72") (name "unconnected-(U7A-RSVD-PadC6)") (class "Default")
      (node (ref "U7") (pin "C6") (pinfunction "RSVD_C6") (pintype "passive+no_connect"))
    )
    (net (code "73") (name "unconnected-(U7A-RSVD-PadC8)") (class "Default")
      (node (ref "U7") (pin "C8") (pinfunction "RSVD_C8") (pintype "passive+no_connect"))
    )
    (net (code "74") (name "unconnected-(U7A-RSVD-PadC10)") (class "Default")
      (node (ref "U7") (pin "C10") (pinfunction "RSVD_C10") (pintype "passive+no_connect"))
    )
    (net (code "75") (name "unconnected-(U7A-RSVD-PadC11)") (class "Default")
      (node (ref "U7") (pin "C11") (pinfunction "RSVD_C11") (pintype "passive+no_connect"))
    )
    (net (code "76") (name "unconnected-(U7A-RSVD-PadC12)") (class "Default")
      (node (ref "U7") (pin "C12") (pinfunction "RSVD_C12") (pintype "passive+no_connect"))
    )
    (net (code "77") (name "unconnected-(U7A-RSVD-PadC13)") (class "Default")
      (node (ref "U7") (pin "C13") (pinfunction "RSVD_C13") (pintype "passive+no_connect"))
    )
    (net (code "78") (name "unconnected-(U7A-RSVD-PadC17)") (class "Default")
      (node (ref "U7") (pin "C17") (pinfunction "RSVD_C17") (pintype "passive+no_connect"))
    )
    (net (code "79") (name "unconnected-(U7A-RSVD-PadC18)") (class "Default")
      (node (ref "U7") (pin "C18") (pinfunction "RSVD_C18") (pintype "passive+no_connect"))
    )
    (net (code "80") (name "unconnected-(U7A-SWITCH_0-PadA6)") (class "Default")
      (node (ref "U7") (pin "A6") (pinfunction "SWITCH_0_A6") (pintype "passive+no_connect"))
    )
    (net (code "81") (name "unconnected-(U7A-UART_CTS-PadA10)") (class "Default")
      (node (ref "U7") (pin "A10") (pinfunction "UART_CTS_A10") (pintype "passive+no_connect"))
    )
    (net (code "82") (name "unconnected-(U7A-UART_DSR-PadA18)") (class "Default")
      (node (ref "U7") (pin "A18") (pinfunction "UART_DSR_A18") (pintype "passive+no_connect"))
    )
    (net (code "83") (name "unconnected-(U7A-UART_DTR-PadA5)") (class "Default")
      (node (ref "U7") (pin "A5") (pinfunction "UART_DTR_A5") (pintype "passive+no_connect"))
    )
    (net (code "84") (name "unconnected-(U7A-UART_RTS-PadA12)") (class "Default")
      (node (ref "U7") (pin "A12") (pinfunction "UART_RTS_A12") (pintype "passive+no_connect"))
    )
    (net (code "85") (name "unconnected-(U7B-RSVD-PadTP1)") (class "Default")
      (node (ref "U7") (pin "TP1") (pinfunction "RSVD_TP1") (pintype "passive+no_connect"))
    )
    (net (code "86") (name "unconnected-(U7B-RSVD-PadTP2)") (class "Default")
      (node (ref "U7") (pin "TP2") (pinfunction "RSVD_TP2") (pintype "passive+no_connect"))
    )
    (net (code "87") (name "unconnected-(U7B-RSVD-PadTP3)") (class "Default")
      (node (ref "U7") (pin "TP3") (pinfunction "RSVD_TP3") (pintype "passive+no_connect"))
    )
    (net (code "88") (name "unconnected-(U7B-RSVD-PadTP4)") (class "Default")
      (node (ref "U7") (pin "TP4") (pinfunction "RSVD_TP4") (pintype "passive+no_connect"))
    )
    (net (code "89") (name "unconnected-(U7B-RSVD-PadTP6)") (class "Default")
      (node (ref "U7") (pin "TP6") (pinfunction "RSVD_TP6") (pintype "passive+no_connect"))
    )
    (net (code "90") (name "unconnected-(U7B-RSVD-PadTP12)") (class "Default")
      (node (ref "U7") (pin "TP12") (pinfunction "RSVD_TP12") (pintype "passive+no_connect"))
    )
    (net (code "91") (name "unconnected-(U7C-RSVD-PadB1)") (class "Default")
      (node (ref "U7") (pin "B1") (pinfunction "RSVD_B1") (pintype "passive+no_connect"))
    )
    (net (code "92") (name "unconnected-(U7C-RSVD-PadB2)") (class "Default")
      (node (ref "U7") (pin "B2") (pinfunction "RSVD_B2") (pintype "passive+no_connect"))
    )
    (net (code "93") (name "unconnected-(U7C-RSVD-PadB3)") (class "Default")
      (node (ref "U7") (pin "B3") (pinfunction "RSVD_B3") (pintype "passive+no_connect"))
    )
    (net (code "94") (name "unconnected-(U7C-RSVD-PadB4)") (class "Default")
      (node (ref "U7") (pin "B4") (pinfunction "RSVD_B4") (pintype "passive+no_connect"))
    )
    (net (code "95") (name "unconnected-(U7C-RSVD-PadB5)") (class "Default")
      (node (ref "U7") (pin "B5") (pinfunction "RSVD_B5") (pintype "passive+no_connect"))
    )
    (net (code "96") (name "unconnected-(U7C-RSVD-PadB6)") (class "Default")
      (node (ref "U7") (pin "B6") (pinfunction "RSVD_B6") (pintype "passive+no_connect"))
    )
    (net (code "97") (name "unconnected-(U7C-RSVD-PadB7)") (class "Default")
      (node (ref "U7") (pin "B7") (pinfunction "RSVD_B7") (pintype "passive+no_connect"))
    )
    (net (code "98") (name "unconnected-(U7C-RSVD-PadB8)") (class "Default")
      (node (ref "U7") (pin "B8") (pinfunction "RSVD_B8") (pintype "passive+no_connect"))
    )
    (net (code "99") (name "unconnected-(U7C-RSVD-PadC2)") (class "Default")
      (node (ref "U7") (pin "C2") (pinfunction "RSVD_C2") (pintype "passive+no_connect"))
    )
    (net (code "100") (name "unconnected-(U7C-RSVD-PadC9)") (class "Default")
      (node (ref "U7") (pin "C9") (pinfunction "RSVD_C9") (pintype "passive+no_connect"))
    )
  )
)
